# ConnectorHolderPCB_V0_3.net
KiCad netlist of a schematic drawn in EAGLE
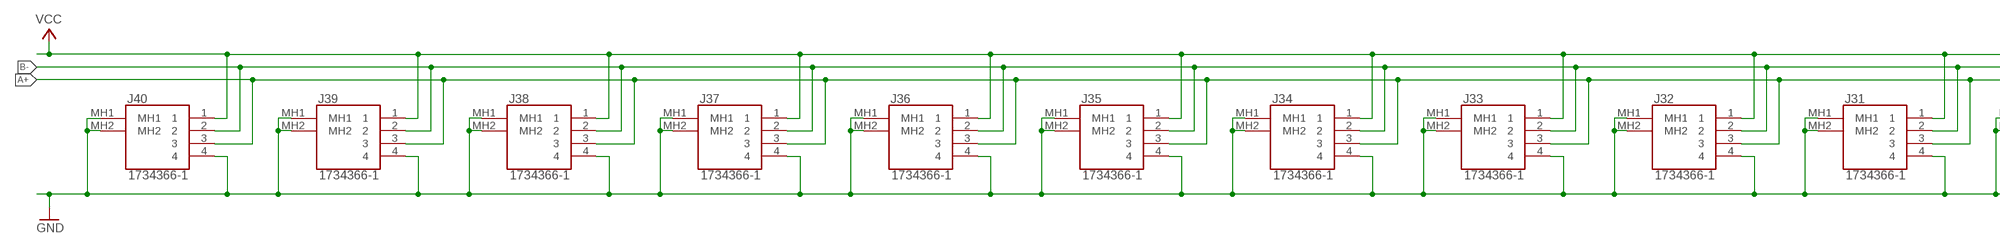
[diagram p0: schematic, sheet 1, part 1 of 2]
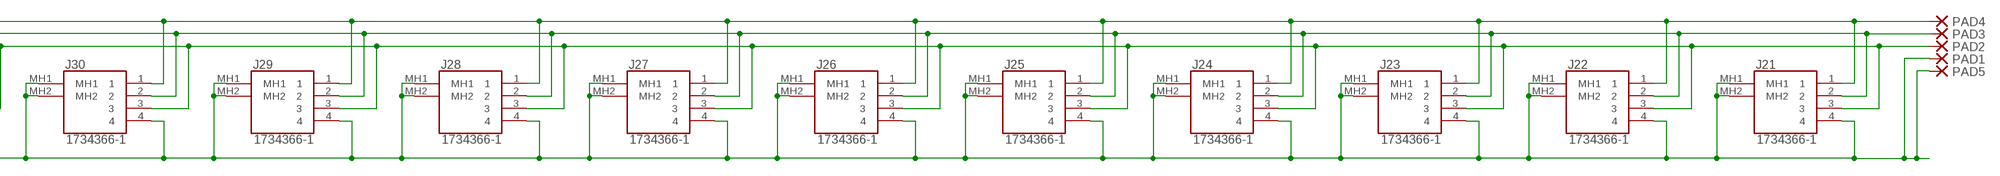
[diagram p1: schematic, sheet 1, part 2 of 2]

(export (version "E")
  (design (tool "Eeschema 10.0.6"))
  (components
    (comp (ref "J21")
      (value "1734366-1")
      (footprint "eagle-import:17343661")
      (fields (field (name "MOUSER_PART_NUMBER") "571-1734366-1"))
      (libsource (lib "eagle-import") (part "1734366-1"))
    )
    (comp (ref "J22")
      (value "1734366-1")
      (footprint "eagle-import:17343661")
      (fields (field (name "MOUSER_PART_NUMBER") "571-1734366-1"))
      (libsource (lib "eagle-import") (part "1734366-1"))
    )
    (comp (ref "J23")
      (value "1734366-1")
      (footprint "eagle-import:17343661")
      (fields (field (name "MOUSER_PART_NUMBER") "571-1734366-1"))
      (libsource (lib "eagle-import") (part "1734366-1"))
    )
    (comp (ref "J24")
      (value "1734366-1")
      (footprint "eagle-import:17343661")
      (fields (field (name "MOUSER_PART_NUMBER") "571-1734366-1"))
      (libsource (lib "eagle-import") (part "1734366-1"))
    )
    (comp (ref "J25")
      (value "1734366-1")
      (footprint "eagle-import:17343661")
      (fields (field (name "MOUSER_PART_NUMBER") "571-1734366-1"))
      (libsource (lib "eagle-import") (part "1734366-1"))
    )
    (comp (ref "J26")
      (value "1734366-1")
      (footprint "eagle-import:17343661")
      (fields (field (name "MOUSER_PART_NUMBER") "571-1734366-1"))
      (libsource (lib "eagle-import") (part "1734366-1"))
    )
    (comp (ref "J27")
      (value "1734366-1")
      (footprint "eagle-import:17343661")
      (fields (field (name "MOUSER_PART_NUMBER") "571-1734366-1"))
      (libsource (lib "eagle-import") (part "1734366-1"))
    )
    (comp (ref "J28")
      (value "1734366-1")
      (footprint "eagle-import:17343661")
      (fields (field (name "MOUSER_PART_NUMBER") "571-1734366-1"))
      (libsource (lib "eagle-import") (part "1734366-1"))
    )
    (comp (ref "J29")
      (value "1734366-1")
      (footprint "eagle-import:17343661")
      (fields (field (name "MOUSER_PART_NUMBER") "571-1734366-1"))
      (libsource (lib "eagle-import") (part "1734366-1"))
    )
    (comp (ref "J30")
      (value "1734366-1")
      (footprint "eagle-import:17343661")
      (fields (field (name "MOUSER_PART_NUMBER") "571-1734366-1"))
      (libsource (lib "eagle-import") (part "1734366-1"))
    )
    (comp (ref "J31")
      (value "1734366-1")
      (footprint "eagle-import:17343661")
      (fields (field (name "MOUSER_PART_NUMBER") "571-1734366-1"))
      (libsource (lib "eagle-import") (part "1734366-1"))
    )
    (comp (ref "J32")
      (value "1734366-1")
      (footprint "eagle-import:17343661")
      (fields (field (name "MOUSER_PART_NUMBER") "571-1734366-1"))
      (libsource (lib "eagle-import") (part "1734366-1"))
    )
    (comp (ref "J33")
      (value "1734366-1")
      (footprint "eagle-import:17343661")
      (fields (field (name "MOUSER_PART_NUMBER") "571-1734366-1"))
      (libsource (lib "eagle-import") (part "1734366-1"))
    )
    (comp (ref "J34")
      (value "1734366-1")
      (footprint "eagle-import:17343661")
      (fields (field (name "MOUSER_PART_NUMBER") "571-1734366-1"))
      (libsource (lib "eagle-import") (part "1734366-1"))
    )
    (comp (ref "J35")
      (value "1734366-1")
      (footprint "eagle-import:17343661")
      (fields (field (name "MOUSER_PART_NUMBER") "571-1734366-1"))
      (libsource (lib "eagle-import") (part "1734366-1"))
    )
    (comp (ref "J36")
      (value "1734366-1")
      (footprint "eagle-import:17343661")
      (fields (field (name "MOUSER_PART_NUMBER") "571-1734366-1"))
      (libsource (lib "eagle-import") (part "1734366-1"))
    )
    (comp (ref "J37")
      (value "1734366-1")
      (footprint "eagle-import:17343661")
      (fields (field (name "MOUSER_PART_NUMBER") "571-1734366-1"))
      (libsource (lib "eagle-import") (part "1734366-1"))
    )
    (comp (ref "J38")
      (value "1734366-1")
      (footprint "eagle-import:17343661")
      (fields (field (name "MOUSER_PART_NUMBER") "571-1734366-1"))
      (libsource (lib "eagle-import") (part "1734366-1"))
    )
    (comp (ref "J39")
      (value "1734366-1")
      (footprint "eagle-import:17343661")
      (fields (field (name "MOUSER_PART_NUMBER") "571-1734366-1"))
      (libsource (lib "eagle-import") (part "1734366-1"))
    )
    (comp (ref "J40")
      (value "1734366-1")
      (footprint "eagle-import:17343661")
      (fields (field (name "MOUSER_PART_NUMBER") "571-1734366-1"))
      (libsource (lib "eagle-import") (part "1734366-1"))
    )
    (comp (ref "PAD1")
      (value "SMD2")
      (footprint "eagle-import:SMD1,27-2,54")
      (libsource (lib "eagle-import") (part "SMD2"))
    )
    (comp (ref "PAD2")
      (value "SMD2")
      (footprint "eagle-import:SMD1,27-2,54")
      (libsource (lib "eagle-import") (part "SMD2"))
    )
    (comp (ref "PAD3")
      (value "SMD2")
      (footprint "eagle-import:SMD1,27-2,54")
      (libsource (lib "eagle-import") (part "SMD2"))
    )
    (comp (ref "PAD4")
      (value "SMD2")
      (footprint "eagle-import:SMD1,27-2,54")
      (libsource (lib "eagle-import") (part "SMD2"))
    )
    (comp (ref "PAD5")
      (value "SMD2")
      (footprint "eagle-import:SMD1,27-2,54")
      (libsource (lib "eagle-import") (part "SMD2"))
    )
  )
  (nets
    (net (code "1") (name "A+") (class "Default")
      (node (ref "J21") (pin "3") (pinfunction "3_3") (pintype "bidirectional"))
      (node (ref "J22") (pin "3") (pinfunction "3_3") (pintype "bidirectional"))
      (node (ref "J23") (pin "3") (pinfunction "3_3") (pintype "bidirectional"))
      (node (ref "J24") (pin "3") (pinfunction "3_3") (pintype "bidirectional"))
      (node (ref "J25") (pin "3") (pinfunction "3_3") (pintype "bidirectional"))
      (node (ref "J26") (pin "3") (pinfunction "3_3") (pintype "bidirectional"))
      (node (ref "J27") (pin "3") (pinfunction "3_3") (pintype "bidirectional"))
      (node (ref "J28") (pin "3") (pinfunction "3_3") (pintype "bidirectional"))
      (node (ref "J29") (pin "3") (pinfunction "3_3") (pintype "bidirectional"))
      (node (ref "J30") (pin "3") (pinfunction "3_3") (pintype "bidirectional"))
      (node (ref "J31") (pin "3") (pinfunction "3_3") (pintype "bidirectional"))
      (node (ref "J32") (pin "3") (pinfunction "3_3") (pintype "bidirectional"))
      (node (ref "J33") (pin "3") (pinfunction "3_3") (pintype "bidirectional"))
      (node (ref "J34") (pin "3") (pinfunction "3_3") (pintype "bidirectional"))
      (node (ref "J35") (pin "3") (pinfunction "3_3") (pintype "bidirectional"))
      (node (ref "J36") (pin "3") (pinfunction "3_3") (pintype "bidirectional"))
      (node (ref "J37") (pin "3") (pinfunction "3_3") (pintype "bidirectional"))
      (node (ref "J38") (pin "3") (pinfunction "3_3") (pintype "bidirectional"))
      (node (ref "J39") (pin "3") (pinfunction "3_3") (pintype "bidirectional"))
      (node (ref "J40") (pin "3") (pinfunction "3_3") (pintype "bidirectional"))
      (node (ref "PAD2") (pin "1") (pinfunction "P_1") (pintype "passive"))
    )
    (net (code "2") (name "B-") (class "Default")
      (node (ref "J21") (pin "2") (pinfunction "2_2") (pintype "bidirectional"))
      (node (ref "J22") (pin "2") (pinfunction "2_2") (pintype "bidirectional"))
      (node (ref "J23") (pin "2") (pinfunction "2_2") (pintype "bidirectional"))
      (node (ref "J24") (pin "2") (pinfunction "2_2") (pintype "bidirectional"))
      (node (ref "J25") (pin "2") (pinfunction "2_2") (pintype "bidirectional"))
      (node (ref "J26") (pin "2") (pinfunction "2_2") (pintype "bidirectional"))
      (node (ref "J27") (pin "2") (pinfunction "2_2") (pintype "bidirectional"))
      (node (ref "J28") (pin "2") (pinfunction "2_2") (pintype "bidirectional"))
      (node (ref "J29") (pin "2") (pinfunction "2_2") (pintype "bidirectional"))
      (node (ref "J30") (pin "2") (pinfunction "2_2") (pintype "bidirectional"))
      (node (ref "J31") (pin "2") (pinfunction "2_2") (pintype "bidirectional"))
      (node (ref "J32") (pin "2") (pinfunction "2_2") (pintype "bidirectional"))
      (node (ref "J33") (pin "2") (pinfunction "2_2") (pintype "bidirectional"))
      (node (ref "J34") (pin "2") (pinfunction "2_2") (pintype "bidirectional"))
      (node (ref "J35") (pin "2") (pinfunction "2_2") (pintype "bidirectional"))
      (node (ref "J36") (pin "2") (pinfunction "2_2") (pintype "bidirectional"))
      (node (ref "J37") (pin "2") (pinfunction "2_2") (pintype "bidirectional"))
      (node (ref "J38") (pin "2") (pinfunction "2_2") (pintype "bidirectional"))
      (node (ref "J39") (pin "2") (pinfunction "2_2") (pintype "bidirectional"))
      (node (ref "J40") (pin "2") (pinfunction "2_2") (pintype "bidirectional"))
      (node (ref "PAD3") (pin "1") (pinfunction "P_1") (pintype "passive"))
    )
    (net (code "3") (name "GND") (class "Default")
      (node (ref "J21") (pin "4") (pinfunction "4_4") (pintype "bidirectional"))
      (node (ref "J21") (pin "MH1") (pinfunction "MH1_MH1") (pintype "bidirectional"))
      (node (ref "J21") (pin "MH2") (pinfunction "MH2_MH2") (pintype "bidirectional"))
      (node (ref "J22") (pin "4") (pinfunction "4_4") (pintype "bidirectional"))
      (node (ref "J22") (pin "MH1") (pinfunction "MH1_MH1") (pintype "bidirectional"))
      (node (ref "J22") (pin "MH2") (pinfunction "MH2_MH2") (pintype "bidirectional"))
      (node (ref "J23") (pin "4") (pinfunction "4_4") (pintype "bidirectional"))
      (node (ref "J23") (pin "MH1") (pinfunction "MH1_MH1") (pintype "bidirectional"))
      (node (ref "J23") (pin "MH2") (pinfunction "MH2_MH2") (pintype "bidirectional"))
      (node (ref "J24") (pin "4") (pinfunction "4_4") (pintype "bidirectional"))
      (node (ref "J24") (pin "MH1") (pinfunction "MH1_MH1") (pintype "bidirectional"))
      (node (ref "J24") (pin "MH2") (pinfunction "MH2_MH2") (pintype "bidirectional"))
      (node (ref "J25") (pin "4") (pinfunction "4_4") (pintype "bidirectional"))
      (node (ref "J25") (pin "MH1") (pinfunction "MH1_MH1") (pintype "bidirectional"))
      (node (ref "J25") (pin "MH2") (pinfunction "MH2_MH2") (pintype "bidirectional"))
      (node (ref "J26") (pin "4") (pinfunction "4_4") (pintype "bidirectional"))
      (node (ref "J26") (pin "MH1") (pinfunction "MH1_MH1") (pintype "bidirectional"))
      (node (ref "J26") (pin "MH2") (pinfunction "MH2_MH2") (pintype "bidirectional"))
      (node (ref "J27") (pin "4") (pinfunction "4_4") (pintype "bidirectional"))
      (node (ref "J27") (pin "MH1") (pinfunction "MH1_MH1") (pintype "bidirectional"))
      (node (ref "J27") (pin "MH2") (pinfunction "MH2_MH2") (pintype "bidirectional"))
      (node (ref "J28") (pin "4") (pinfunction "4_4") (pintype "bidirectional"))
      (node (ref "J28") (pin "MH1") (pinfunction "MH1_MH1") (pintype "bidirectional"))
      (node (ref "J28") (pin "MH2") (pinfunction "MH2_MH2") (pintype "bidirectional"))
      (node (ref "J29") (pin "4") (pinfunction "4_4") (pintype "bidirectional"))
      (node (ref "J29") (pin "MH1") (pinfunction "MH1_MH1") (pintype "bidirectional"))
      (node (ref "J29") (pin "MH2") (pinfunction "MH2_MH2") (pintype "bidirectional"))
      (node (ref "J30") (pin "4") (pinfunction "4_4") (pintype "bidirectional"))
      (node (ref "J30") (pin "MH1") (pinfunction "MH1_MH1") (pintype "bidirectional"))
      (node (ref "J30") (pin "MH2") (pinfunction "MH2_MH2") (pintype "bidirectional"))
      (node (ref "J31") (pin "4") (pinfunction "4_4") (pintype "bidirectional"))
      (node (ref "J31") (pin "MH1") (pinfunction "MH1_MH1") (pintype "bidirectional"))
      (node (ref "J31") (pin "MH2") (pinfunction "MH2_MH2") (pintype "bidirectional"))
      (node (ref "J32") (pin "4") (pinfunction "4_4") (pintype "bidirectional"))
      (node (ref "J32") (pin "MH1") (pinfunction "MH1_MH1") (pintype "bidirectional"))
      (node (ref "J32") (pin "MH2") (pinfunction "MH2_MH2") (pintype "bidirectional"))
      (node (ref "J33") (pin "4") (pinfunction "4_4") (pintype "bidirectional"))
      (node (ref "J33") (pin "MH1") (pinfunction "MH1_MH1") (pintype "bidirectional"))
      (node (ref "J33") (pin "MH2") (pinfunction "MH2_MH2") (pintype "bidirectional"))
      (node (ref "J34") (pin "4") (pinfunction "4_4") (pintype "bidirectional"))
      (node (ref "J34") (pin "MH1") (pinfunction "MH1_MH1") (pintype "bidirectional"))
      (node (ref "J34") (pin "MH2") (pinfunction "MH2_MH2") (pintype "bidirectional"))
      (node (ref "J35") (pin "4") (pinfunction "4_4") (pintype "bidirectional"))
      (node (ref "J35") (pin "MH1") (pinfunction "MH1_MH1") (pintype "bidirectional"))
      (node (ref "J35") (pin "MH2") (pinfunction "MH2_MH2") (pintype "bidirectional"))
      (node (ref "J36") (pin "4") (pinfunction "4_4") (pintype "bidirectional"))
      (node (ref "J36") (pin "MH1") (pinfunction "MH1_MH1") (pintype "bidirectional"))
      (node (ref "J36") (pin "MH2") (pinfunction "MH2_MH2") (pintype "bidirectional"))
      (node (ref "J37") (pin "4") (pinfunction "4_4") (pintype "bidirectional"))
      (node (ref "J37") (pin "MH1") (pinfunction "MH1_MH1") (pintype "bidirectional"))
      (node (ref "J37") (pin "MH2") (pinfunction "MH2_MH2") (pintype "bidirectional"))
      (node (ref "J38") (pin "4") (pinfunction "4_4") (pintype "bidirectional"))
      (node (ref "J38") (pin "MH1") (pinfunction "MH1_MH1") (pintype "bidirectional"))
      (node (ref "J38") (pin "MH2") (pinfunction "MH2_MH2") (pintype "bidirectional"))
      (node (ref "J39") (pin "4") (pinfunction "4_4") (pintype "bidirectional"))
      (node (ref "J39") (pin "MH1") (pinfunction "MH1_MH1") (pintype "bidirectional"))
      (node (ref "J39") (pin "MH2") (pinfunction "MH2_MH2") (pintype "bidirectional"))
      (node (ref "J40") (pin "4") (pinfunction "4_4") (pintype "bidirectional"))
      (node (ref "J40") (pin "MH1") (pinfunction "MH1_MH1") (pintype "bidirectional"))
      (node (ref "J40") (pin "MH2") (pinfunction "MH2_MH2") (pintype "bidirectional"))
      (node (ref "PAD1") (pin "1") (pinfunction "P_1") (pintype "passive"))
      (node (ref "PAD5") (pin "1") (pinfunction "P_1") (pintype "passive"))
    )
    (net (code "4") (name "VCC") (class "Default")
      (node (ref "J21") (pin "1") (pinfunction "1_1") (pintype "bidirectional"))
      (node (ref "J22") (pin "1") (pinfunction "1_1") (pintype "bidirectional"))
      (node (ref "J23") (pin "1") (pinfunction "1_1") (pintype "bidirectional"))
      (node (ref "J24") (pin "1") (pinfunction "1_1") (pintype "bidirectional"))
      (node (ref "J25") (pin "1") (pinfunction "1_1") (pintype "bidirectional"))
      (node (ref "J26") (pin "1") (pinfunction "1_1") (pintype "bidirectional"))
      (node (ref "J27") (pin "1") (pinfunction "1_1") (pintype "bidirectional"))
      (node (ref "J28") (pin "1") (pinfunction "1_1") (pintype "bidirectional"))
      (node (ref "J29") (pin "1") (pinfunction "1_1") (pintype "bidirectional"))
      (node (ref "J30") (pin "1") (pinfunction "1_1") (pintype "bidirectional"))
      (node (ref "J31") (pin "1") (pinfunction "1_1") (pintype "bidirectional"))
      (node (ref "J32") (pin "1") (pinfunction "1_1") (pintype "bidirectional"))
      (node (ref "J33") (pin "1") (pinfunction "1_1") (pintype "bidirectional"))
      (node (ref "J34") (pin "1") (pinfunction "1_1") (pintype "bidirectional"))
      (node (ref "J35") (pin "1") (pinfunction "1_1") (pintype "bidirectional"))
      (node (ref "J36") (pin "1") (pinfunction "1_1") (pintype "bidirectional"))
      (node (ref "J37") (pin "1") (pinfunction "1_1") (pintype "bidirectional"))
      (node (ref "J38") (pin "1") (pinfunction "1_1") (pintype "bidirectional"))
      (node (ref "J39") (pin "1") (pinfunction "1_1") (pintype "bidirectional"))
      (node (ref "J40") (pin "1") (pinfunction "1_1") (pintype "bidirectional"))
      (node (ref "PAD4") (pin "1") (pinfunction "P_1") (pintype "passive"))
    )
  )
)
